# tron_disc.net
KiCad netlist of a schematic drawn in EAGLE
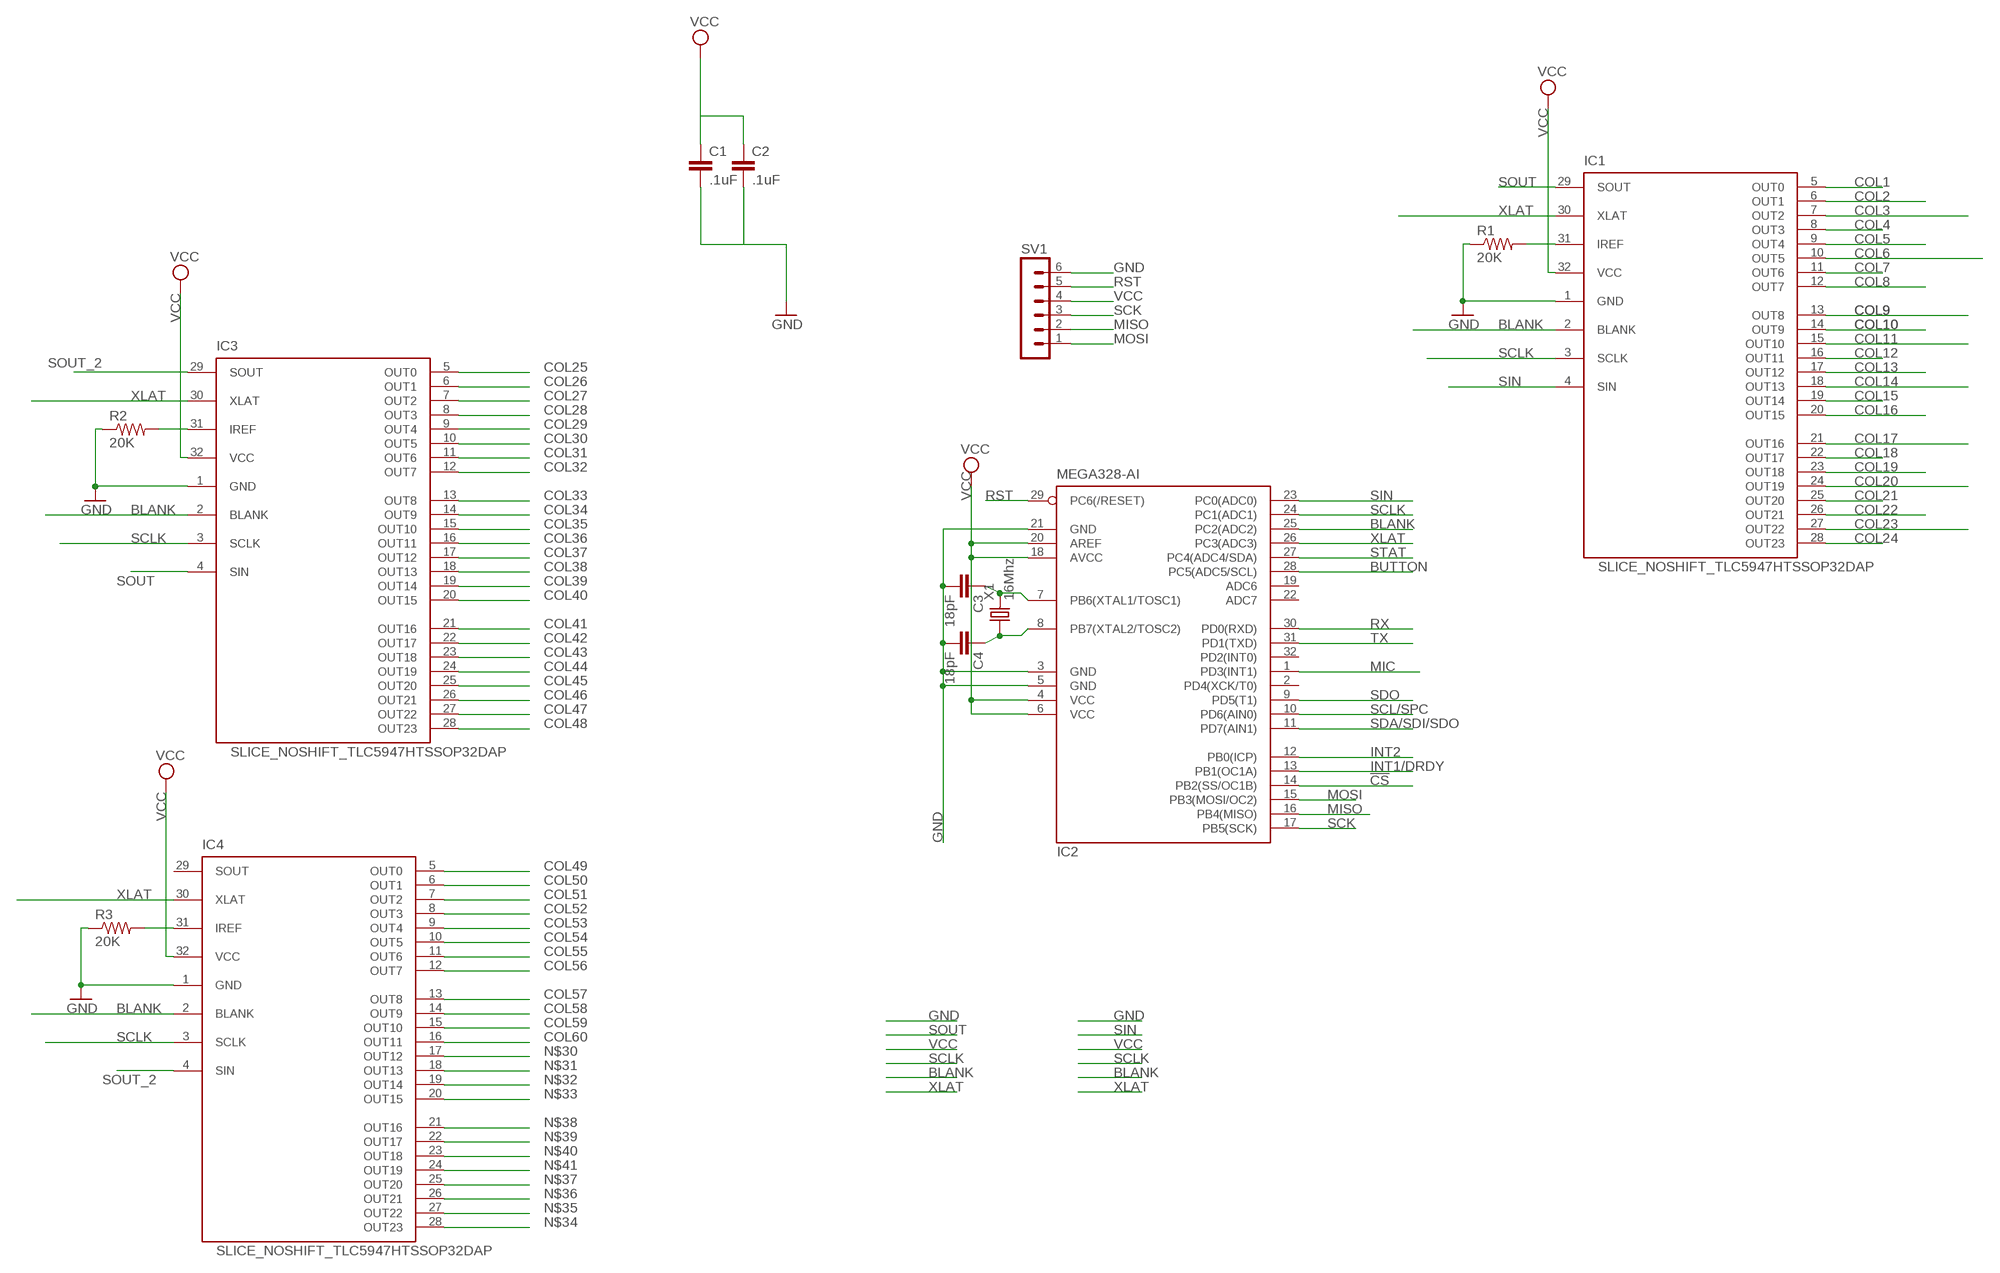
[diagram p0: schematic, sheet 1]
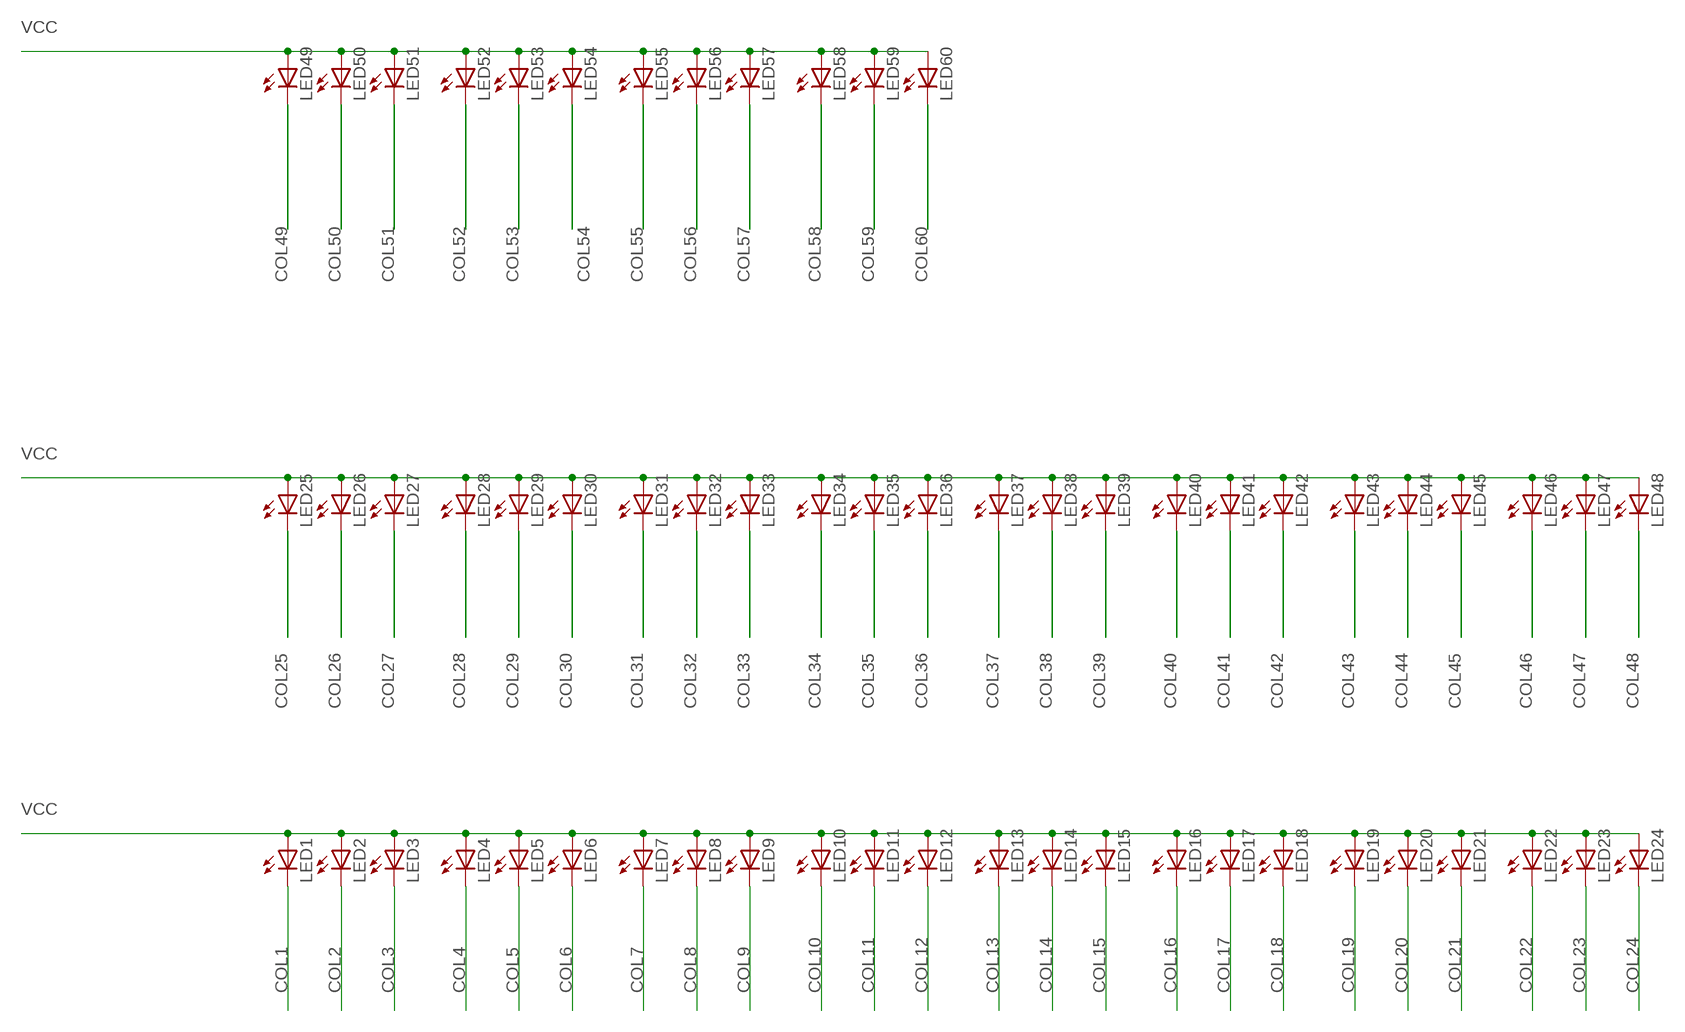
[diagram p1: schematic, sheet 2]
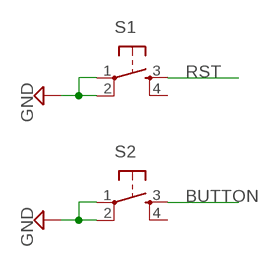
[diagram p2: schematic, sheet 3]

(export (version "E")
  (design (tool "Eeschema 10.0.6"))
  (components
    (comp (ref "S1")
      (value "TAC_SWITCHSMD")
      (footprint "eagle-import:TACTILE_SWITCH_SMD")
      (libsource (lib "eagle-import") (part "TAC_SWITCHSMD"))
    )
    (comp (ref "S2")
      (value "TAC_SWITCHSMD")
      (footprint "eagle-import:TACTILE_SWITCH_SMD")
      (libsource (lib "eagle-import") (part "TAC_SWITCHSMD"))
    )
    (comp (ref "C1")
      (value ".1uF")
      (footprint "eagle-import:0805")
      (libsource (lib "eagle-import") (part "CAP0805"))
    )
    (comp (ref "C2")
      (value ".1uF")
      (footprint "eagle-import:0805")
      (libsource (lib "eagle-import") (part "CAP0805"))
    )
    (comp (ref "C3")
      (value "18pF")
      (footprint "eagle-import:0805")
      (libsource (lib "eagle-import") (part "CAP0805"))
    )
    (comp (ref "C4")
      (value "18pF")
      (footprint "eagle-import:0805")
      (libsource (lib "eagle-import") (part "CAP0805"))
    )
    (comp (ref "IC1")
      (value "SLICE_NOSHIFT_TLC5947HTSSOP32DAP")
      (footprint "eagle-import:HTSSOP32DAP")
      (libsource (lib "eagle-import") (part "SLICE_NOSHIFT_TLC5947HTSSOP32DAP"))
    )
    (comp (ref "IC2")
      (value "MEGA328-AI")
      (footprint "eagle-import:TQFP32-08")
      (fields (field (name "MPN") "ATMEGA8-16AU"))
      (libsource (lib "eagle-import") (part "MEGA8-AI"))
    )
    (comp (ref "IC3")
      (value "SLICE_NOSHIFT_TLC5947HTSSOP32DAP")
      (footprint "eagle-import:HTSSOP32DAP")
      (libsource (lib "eagle-import") (part "SLICE_NOSHIFT_TLC5947HTSSOP32DAP"))
    )
    (comp (ref "IC4")
      (value "SLICE_NOSHIFT_TLC5947HTSSOP32DAP")
      (footprint "eagle-import:HTSSOP32DAP")
      (libsource (lib "eagle-import") (part "SLICE_NOSHIFT_TLC5947HTSSOP32DAP"))
    )
    (comp (ref "R1")
      (value "20K")
      (footprint "eagle-import:R0805")
      (libsource (lib "eagle-import") (part "R-US_R0805"))
    )
    (comp (ref "R2")
      (value "20K")
      (footprint "eagle-import:R0805")
      (libsource (lib "eagle-import") (part "R-US_R0805"))
    )
    (comp (ref "R3")
      (value "20K")
      (footprint "eagle-import:R0805")
      (libsource (lib "eagle-import") (part "R-US_R0805"))
    )
    (comp (ref "SV1")
      (value "MA06-1")
      (footprint "eagle-import:MA06-1")
      (libsource (lib "eagle-import") (part "MA06-1"))
    )
    (comp (ref "X1")
      (value "16Mhz")
      (footprint "eagle-import:5032")
      (libsource (lib "eagle-import") (part "CRYSTAL-5032"))
    )
    (comp (ref "LED1")
      (value "LEDCHIPLED_1206")
      (footprint "eagle-import:CHIPLED_1206")
      (libsource (lib "eagle-import") (part "LEDCHIPLED_1206"))
    )
    (comp (ref "LED2")
      (value "LEDCHIPLED_1206")
      (footprint "eagle-import:CHIPLED_1206")
      (libsource (lib "eagle-import") (part "LEDCHIPLED_1206"))
    )
    (comp (ref "LED3")
      (value "LEDCHIPLED_1206")
      (footprint "eagle-import:CHIPLED_1206")
      (libsource (lib "eagle-import") (part "LEDCHIPLED_1206"))
    )
    (comp (ref "LED4")
      (value "LEDCHIPLED_1206")
      (footprint "eagle-import:CHIPLED_1206")
      (libsource (lib "eagle-import") (part "LEDCHIPLED_1206"))
    )
    (comp (ref "LED5")
      (value "LEDCHIPLED_1206")
      (footprint "eagle-import:CHIPLED_1206")
      (libsource (lib "eagle-import") (part "LEDCHIPLED_1206"))
    )
    (comp (ref "LED6")
      (value "LEDCHIPLED_1206")
      (footprint "eagle-import:CHIPLED_1206")
      (libsource (lib "eagle-import") (part "LEDCHIPLED_1206"))
    )
    (comp (ref "LED7")
      (value "LEDCHIPLED_1206")
      (footprint "eagle-import:CHIPLED_1206")
      (libsource (lib "eagle-import") (part "LEDCHIPLED_1206"))
    )
    (comp (ref "LED8")
      (value "LEDCHIPLED_1206")
      (footprint "eagle-import:CHIPLED_1206")
      (libsource (lib "eagle-import") (part "LEDCHIPLED_1206"))
    )
    (comp (ref "LED9")
      (value "LEDCHIPLED_1206")
      (footprint "eagle-import:CHIPLED_1206")
      (libsource (lib "eagle-import") (part "LEDCHIPLED_1206"))
    )
    (comp (ref "LED10")
      (value "LEDCHIPLED_1206")
      (footprint "eagle-import:CHIPLED_1206")
      (libsource (lib "eagle-import") (part "LEDCHIPLED_1206"))
    )
    (comp (ref "LED11")
      (value "LEDCHIPLED_1206")
      (footprint "eagle-import:CHIPLED_1206")
      (libsource (lib "eagle-import") (part "LEDCHIPLED_1206"))
    )
    (comp (ref "LED12")
      (value "LEDCHIPLED_1206")
      (footprint "eagle-import:CHIPLED_1206")
      (libsource (lib "eagle-import") (part "LEDCHIPLED_1206"))
    )
    (comp (ref "LED13")
      (value "LEDCHIPLED_1206")
      (footprint "eagle-import:CHIPLED_1206")
      (libsource (lib "eagle-import") (part "LEDCHIPLED_1206"))
    )
    (comp (ref "LED14")
      (value "LEDCHIPLED_1206")
      (footprint "eagle-import:CHIPLED_1206")
      (libsource (lib "eagle-import") (part "LEDCHIPLED_1206"))
    )
    (comp (ref "LED15")
      (value "LEDCHIPLED_1206")
      (footprint "eagle-import:CHIPLED_1206")
      (libsource (lib "eagle-import") (part "LEDCHIPLED_1206"))
    )
    (comp (ref "LED16")
      (value "LEDCHIPLED_1206")
      (footprint "eagle-import:CHIPLED_1206")
      (libsource (lib "eagle-import") (part "LEDCHIPLED_1206"))
    )
    (comp (ref "LED17")
      (value "LEDCHIPLED_1206")
      (footprint "eagle-import:CHIPLED_1206")
      (libsource (lib "eagle-import") (part "LEDCHIPLED_1206"))
    )
    (comp (ref "LED18")
      (value "LEDCHIPLED_1206")
      (footprint "eagle-import:CHIPLED_1206")
      (libsource (lib "eagle-import") (part "LEDCHIPLED_1206"))
    )
    (comp (ref "LED19")
      (value "LEDCHIPLED_1206")
      (footprint "eagle-import:CHIPLED_1206")
      (libsource (lib "eagle-import") (part "LEDCHIPLED_1206"))
    )
    (comp (ref "LED20")
      (value "LEDCHIPLED_1206")
      (footprint "eagle-import:CHIPLED_1206")
      (libsource (lib "eagle-import") (part "LEDCHIPLED_1206"))
    )
    (comp (ref "LED21")
      (value "LEDCHIPLED_1206")
      (footprint "eagle-import:CHIPLED_1206")
      (libsource (lib "eagle-import") (part "LEDCHIPLED_1206"))
    )
    (comp (ref "LED22")
      (value "LEDCHIPLED_1206")
      (footprint "eagle-import:CHIPLED_1206")
      (libsource (lib "eagle-import") (part "LEDCHIPLED_1206"))
    )
    (comp (ref "LED23")
      (value "LEDCHIPLED_1206")
      (footprint "eagle-import:CHIPLED_1206")
      (libsource (lib "eagle-import") (part "LEDCHIPLED_1206"))
    )
    (comp (ref "LED24")
      (value "LEDCHIPLED_1206")
      (footprint "eagle-import:CHIPLED_1206")
      (libsource (lib "eagle-import") (part "LEDCHIPLED_1206"))
    )
    (comp (ref "LED25")
      (value "LEDCHIPLED_1206")
      (footprint "eagle-import:CHIPLED_1206")
      (libsource (lib "eagle-import") (part "LEDCHIPLED_1206"))
    )
    (comp (ref "LED26")
      (value "LEDCHIPLED_1206")
      (footprint "eagle-import:CHIPLED_1206")
      (libsource (lib "eagle-import") (part "LEDCHIPLED_1206"))
    )
    (comp (ref "LED27")
      (value "LEDCHIPLED_1206")
      (footprint "eagle-import:CHIPLED_1206")
      (libsource (lib "eagle-import") (part "LEDCHIPLED_1206"))
    )
    (comp (ref "LED28")
      (value "LEDCHIPLED_1206")
      (footprint "eagle-import:CHIPLED_1206")
      (libsource (lib "eagle-import") (part "LEDCHIPLED_1206"))
    )
    (comp (ref "LED29")
      (value "LEDCHIPLED_1206")
      (footprint "eagle-import:CHIPLED_1206")
      (libsource (lib "eagle-import") (part "LEDCHIPLED_1206"))
    )
    (comp (ref "LED30")
      (value "LEDCHIPLED_1206")
      (footprint "eagle-import:CHIPLED_1206")
      (libsource (lib "eagle-import") (part "LEDCHIPLED_1206"))
    )
    (comp (ref "LED31")
      (value "LEDCHIPLED_1206")
      (footprint "eagle-import:CHIPLED_1206")
      (libsource (lib "eagle-import") (part "LEDCHIPLED_1206"))
    )
    (comp (ref "LED32")
      (value "LEDCHIPLED_1206")
      (footprint "eagle-import:CHIPLED_1206")
      (libsource (lib "eagle-import") (part "LEDCHIPLED_1206"))
    )
    (comp (ref "LED33")
      (value "LEDCHIPLED_1206")
      (footprint "eagle-import:CHIPLED_1206")
      (libsource (lib "eagle-import") (part "LEDCHIPLED_1206"))
    )
    (comp (ref "LED34")
      (value "LEDCHIPLED_1206")
      (footprint "eagle-import:CHIPLED_1206")
      (libsource (lib "eagle-import") (part "LEDCHIPLED_1206"))
    )
    (comp (ref "LED35")
      (value "LEDCHIPLED_1206")
      (footprint "eagle-import:CHIPLED_1206")
      (libsource (lib "eagle-import") (part "LEDCHIPLED_1206"))
    )
    (comp (ref "LED36")
      (value "LEDCHIPLED_1206")
      (footprint "eagle-import:CHIPLED_1206")
      (libsource (lib "eagle-import") (part "LEDCHIPLED_1206"))
    )
    (comp (ref "LED37")
      (value "LEDCHIPLED_1206")
      (footprint "eagle-import:CHIPLED_1206")
      (libsource (lib "eagle-import") (part "LEDCHIPLED_1206"))
    )
    (comp (ref "LED38")
      (value "LEDCHIPLED_1206")
      (footprint "eagle-import:CHIPLED_1206")
      (libsource (lib "eagle-import") (part "LEDCHIPLED_1206"))
    )
    (comp (ref "LED39")
      (value "LEDCHIPLED_1206")
      (footprint "eagle-import:CHIPLED_1206")
      (libsource (lib "eagle-import") (part "LEDCHIPLED_1206"))
    )
    (comp (ref "LED40")
      (value "LEDCHIPLED_1206")
      (footprint "eagle-import:CHIPLED_1206")
      (libsource (lib "eagle-import") (part "LEDCHIPLED_1206"))
    )
    (comp (ref "LED41")
      (value "LEDCHIPLED_1206")
      (footprint "eagle-import:CHIPLED_1206")
      (libsource (lib "eagle-import") (part "LEDCHIPLED_1206"))
    )
    (comp (ref "LED42")
      (value "LEDCHIPLED_1206")
      (footprint "eagle-import:CHIPLED_1206")
      (libsource (lib "eagle-import") (part "LEDCHIPLED_1206"))
    )
    (comp (ref "LED43")
      (value "LEDCHIPLED_1206")
      (footprint "eagle-import:CHIPLED_1206")
      (libsource (lib "eagle-import") (part "LEDCHIPLED_1206"))
    )
    (comp (ref "LED44")
      (value "LEDCHIPLED_1206")
      (footprint "eagle-import:CHIPLED_1206")
      (libsource (lib "eagle-import") (part "LEDCHIPLED_1206"))
    )
    (comp (ref "LED45")
      (value "LEDCHIPLED_1206")
      (footprint "eagle-import:CHIPLED_1206")
      (libsource (lib "eagle-import") (part "LEDCHIPLED_1206"))
    )
    (comp (ref "LED46")
      (value "LEDCHIPLED_1206")
      (footprint "eagle-import:CHIPLED_1206")
      (libsource (lib "eagle-import") (part "LEDCHIPLED_1206"))
    )
    (comp (ref "LED47")
      (value "LEDCHIPLED_1206")
      (footprint "eagle-import:CHIPLED_1206")
      (libsource (lib "eagle-import") (part "LEDCHIPLED_1206"))
    )
    (comp (ref "LED48")
      (value "LEDCHIPLED_1206")
      (footprint "eagle-import:CHIPLED_1206")
      (libsource (lib "eagle-import") (part "LEDCHIPLED_1206"))
    )
    (comp (ref "LED49")
      (value "LEDCHIPLED_1206")
      (footprint "eagle-import:CHIPLED_1206")
      (libsource (lib "eagle-import") (part "LEDCHIPLED_1206"))
    )
    (comp (ref "LED50")
      (value "LEDCHIPLED_1206")
      (footprint "eagle-import:CHIPLED_1206")
      (libsource (lib "eagle-import") (part "LEDCHIPLED_1206"))
    )
    (comp (ref "LED51")
      (value "LEDCHIPLED_1206")
      (footprint "eagle-import:CHIPLED_1206")
      (libsource (lib "eagle-import") (part "LEDCHIPLED_1206"))
    )
    (comp (ref "LED52")
      (value "LEDCHIPLED_1206")
      (footprint "eagle-import:CHIPLED_1206")
      (libsource (lib "eagle-import") (part "LEDCHIPLED_1206"))
    )
    (comp (ref "LED53")
      (value "LEDCHIPLED_1206")
      (footprint "eagle-import:CHIPLED_1206")
      (libsource (lib "eagle-import") (part "LEDCHIPLED_1206"))
    )
    (comp (ref "LED54")
      (value "LEDCHIPLED_1206")
      (footprint "eagle-import:CHIPLED_1206")
      (libsource (lib "eagle-import") (part "LEDCHIPLED_1206"))
    )
    (comp (ref "LED55")
      (value "LEDCHIPLED_1206")
      (footprint "eagle-import:CHIPLED_1206")
      (libsource (lib "eagle-import") (part "LEDCHIPLED_1206"))
    )
    (comp (ref "LED56")
      (value "LEDCHIPLED_1206")
      (footprint "eagle-import:CHIPLED_1206")
      (libsource (lib "eagle-import") (part "LEDCHIPLED_1206"))
    )
    (comp (ref "LED57")
      (value "LEDCHIPLED_1206")
      (footprint "eagle-import:CHIPLED_1206")
      (libsource (lib "eagle-import") (part "LEDCHIPLED_1206"))
    )
    (comp (ref "LED58")
      (value "LEDCHIPLED_1206")
      (footprint "eagle-import:CHIPLED_1206")
      (libsource (lib "eagle-import") (part "LEDCHIPLED_1206"))
    )
    (comp (ref "LED59")
      (value "LEDCHIPLED_1206")
      (footprint "eagle-import:CHIPLED_1206")
      (libsource (lib "eagle-import") (part "LEDCHIPLED_1206"))
    )
    (comp (ref "LED60")
      (value "LEDCHIPLED_1206")
      (footprint "eagle-import:CHIPLED_1206")
      (libsource (lib "eagle-import") (part "LEDCHIPLED_1206"))
    )
  )
  (nets
    (net (code "1") (name "BLANK") (class "Default")
      (node (ref "IC1") (pin "2") (pinfunction "BLANK_2") (pintype "bidirectional"))
      (node (ref "IC2") (pin "25") (pinfunction "PC2(ADC2)_25") (pintype "bidirectional"))
      (node (ref "IC3") (pin "2") (pinfunction "BLANK_2") (pintype "bidirectional"))
      (node (ref "IC4") (pin "2") (pinfunction "BLANK_2") (pintype "bidirectional"))
    )
    (net (code "2") (name "BUTTON") (class "Default")
      (node (ref "IC2") (pin "28") (pinfunction "PC5(ADC5/SCL)_28") (pintype "bidirectional"))
      (node (ref "S2") (pin "3") (pinfunction "3_3") (pintype "passive"))
    )
    (net (code "3") (name "COL1") (class "Default")
      (node (ref "IC1") (pin "5") (pinfunction "OUT0_5") (pintype "bidirectional"))
      (node (ref "LED1") (pin "C") (pinfunction "C_C") (pintype "passive"))
    )
    (net (code "4") (name "COL2") (class "Default")
      (node (ref "IC1") (pin "6") (pinfunction "OUT1_6") (pintype "bidirectional"))
      (node (ref "LED2") (pin "C") (pinfunction "C_C") (pintype "passive"))
    )
    (net (code "5") (name "COL3") (class "Default")
      (node (ref "IC1") (pin "7") (pinfunction "OUT2_7") (pintype "bidirectional"))
      (node (ref "LED3") (pin "C") (pinfunction "C_C") (pintype "passive"))
    )
    (net (code "6") (name "COL4") (class "Default")
      (node (ref "IC1") (pin "8") (pinfunction "OUT3_8") (pintype "bidirectional"))
      (node (ref "LED4") (pin "C") (pinfunction "C_C") (pintype "passive"))
    )
    (net (code "7") (name "COL5") (class "Default")
      (node (ref "IC1") (pin "9") (pinfunction "OUT4_9") (pintype "bidirectional"))
      (node (ref "LED5") (pin "C") (pinfunction "C_C") (pintype "passive"))
    )
    (net (code "8") (name "COL6") (class "Default")
      (node (ref "IC1") (pin "10") (pinfunction "OUT5_10") (pintype "bidirectional"))
      (node (ref "LED6") (pin "C") (pinfunction "C_C") (pintype "passive"))
    )
    (net (code "9") (name "COL7") (class "Default")
      (node (ref "IC1") (pin "11") (pinfunction "OUT6_11") (pintype "bidirectional"))
      (node (ref "LED7") (pin "C") (pinfunction "C_C") (pintype "passive"))
    )
    (net (code "10") (name "COL8") (class "Default")
      (node (ref "IC1") (pin "12") (pinfunction "OUT7_12") (pintype "bidirectional"))
      (node (ref "LED8") (pin "C") (pinfunction "C_C") (pintype "passive"))
    )
    (net (code "11") (name "COL9") (class "Default")
      (node (ref "IC1") (pin "13") (pinfunction "OUT8_13") (pintype "bidirectional"))
      (node (ref "LED9") (pin "C") (pinfunction "C_C") (pintype "passive"))
    )
    (net (code "12") (name "COL10") (class "Default")
      (node (ref "IC1") (pin "14") (pinfunction "OUT9_14") (pintype "bidirectional"))
      (node (ref "LED10") (pin "C") (pinfunction "C_C") (pintype "passive"))
    )
    (net (code "13") (name "COL11") (class "Default")
      (node (ref "IC1") (pin "15") (pinfunction "OUT10_15") (pintype "bidirectional"))
      (node (ref "LED11") (pin "C") (pinfunction "C_C") (pintype "passive"))
    )
    (net (code "14") (name "COL12") (class "Default")
      (node (ref "IC1") (pin "16") (pinfunction "OUT11_16") (pintype "bidirectional"))
      (node (ref "LED12") (pin "C") (pinfunction "C_C") (pintype "passive"))
    )
    (net (code "15") (name "COL13") (class "Default")
      (node (ref "IC1") (pin "17") (pinfunction "OUT12_17") (pintype "bidirectional"))
      (node (ref "LED13") (pin "C") (pinfunction "C_C") (pintype "passive"))
    )
    (net (code "16") (name "COL14") (class "Default")
      (node (ref "IC1") (pin "18") (pinfunction "OUT13_18") (pintype "bidirectional"))
      (node (ref "LED14") (pin "C") (pinfunction "C_C") (pintype "passive"))
    )
    (net (code "17") (name "COL15") (class "Default")
      (node (ref "IC1") (pin "19") (pinfunction "OUT14_19") (pintype "bidirectional"))
      (node (ref "LED15") (pin "C") (pinfunction "C_C") (pintype "passive"))
    )
    (net (code "18") (name "COL16") (class "Default")
      (node (ref "IC1") (pin "20") (pinfunction "OUT15_20") (pintype "bidirectional"))
      (node (ref "LED16") (pin "C") (pinfunction "C_C") (pintype "passive"))
    )
    (net (code "19") (name "COL17") (class "Default")
      (node (ref "IC1") (pin "21") (pinfunction "OUT16_21") (pintype "bidirectional"))
      (node (ref "LED17") (pin "C") (pinfunction "C_C") (pintype "passive"))
    )
    (net (code "20") (name "COL18") (class "Default")
      (node (ref "IC1") (pin "22") (pinfunction "OUT17_22") (pintype "bidirectional"))
      (node (ref "LED18") (pin "C") (pinfunction "C_C") (pintype "passive"))
    )
    (net (code "21") (name "COL19") (class "Default")
      (node (ref "IC1") (pin "23") (pinfunction "OUT18_23") (pintype "bidirectional"))
      (node (ref "LED19") (pin "C") (pinfunction "C_C") (pintype "passive"))
    )
    (net (code "22") (name "COL20") (class "Default")
      (node (ref "IC1") (pin "24") (pinfunction "OUT19_24") (pintype "bidirectional"))
      (node (ref "LED20") (pin "C") (pinfunction "C_C") (pintype "passive"))
    )
    (net (code "23") (name "COL21") (class "Default")
      (node (ref "IC1") (pin "25") (pinfunction "OUT20_25") (pintype "bidirectional"))
      (node (ref "LED21") (pin "C") (pinfunction "C_C") (pintype "passive"))
    )
    (net (code "24") (name "COL22") (class "Default")
      (node (ref "IC1") (pin "26") (pinfunction "OUT21_26") (pintype "bidirectional"))
      (node (ref "LED22") (pin "C") (pinfunction "C_C") (pintype "passive"))
    )
    (net (code "25") (name "COL23") (class "Default")
      (node (ref "IC1") (pin "27") (pinfunction "OUT22_27") (pintype "bidirectional"))
      (node (ref "LED23") (pin "C") (pinfunction "C_C") (pintype "passive"))
    )
    (net (code "26") (name "COL24") (class "Default")
      (node (ref "IC1") (pin "28") (pinfunction "OUT23_28") (pintype "bidirectional"))
      (node (ref "LED24") (pin "C") (pinfunction "C_C") (pintype "passive"))
    )
    (net (code "27") (name "COL25") (class "Default")
      (node (ref "IC3") (pin "5") (pinfunction "OUT0_5") (pintype "bidirectional"))
      (node (ref "LED25") (pin "C") (pinfunction "C_C") (pintype "passive"))
    )
    (net (code "28") (name "COL26") (class "Default")
      (node (ref "IC3") (pin "6") (pinfunction "OUT1_6") (pintype "bidirectional"))
      (node (ref "LED26") (pin "C") (pinfunction "C_C") (pintype "passive"))
    )
    (net (code "29") (name "COL27") (class "Default")
      (node (ref "IC3") (pin "7") (pinfunction "OUT2_7") (pintype "bidirectional"))
      (node (ref "LED27") (pin "C") (pinfunction "C_C") (pintype "passive"))
    )
    (net (code "30") (name "COL28") (class "Default")
      (node (ref "IC3") (pin "8") (pinfunction "OUT3_8") (pintype "bidirectional"))
      (node (ref "LED28") (pin "C") (pinfunction "C_C") (pintype "passive"))
    )
    (net (code "31") (name "COL29") (class "Default")
      (node (ref "IC3") (pin "9") (pinfunction "OUT4_9") (pintype "bidirectional"))
      (node (ref "LED29") (pin "C") (pinfunction "C_C") (pintype "passive"))
    )
    (net (code "32") (name "COL30") (class "Default")
      (node (ref "IC3") (pin "10") (pinfunction "OUT5_10") (pintype "bidirectional"))
      (node (ref "LED30") (pin "C") (pinfunction "C_C") (pintype "passive"))
    )
    (net (code "33") (name "COL31") (class "Default")
      (node (ref "IC3") (pin "11") (pinfunction "OUT6_11") (pintype "bidirectional"))
      (node (ref "LED31") (pin "C") (pinfunction "C_C") (pintype "passive"))
    )
    (net (code "34") (name "COL32") (class "Default")
      (node (ref "IC3") (pin "12") (pinfunction "OUT7_12") (pintype "bidirectional"))
      (node (ref "LED32") (pin "C") (pinfunction "C_C") (pintype "passive"))
    )
    (net (code "35") (name "COL33") (class "Default")
      (node (ref "IC3") (pin "13") (pinfunction "OUT8_13") (pintype "bidirectional"))
      (node (ref "LED33") (pin "C") (pinfunction "C_C") (pintype "passive"))
    )
    (net (code "36") (name "COL34") (class "Default")
      (node (ref "IC3") (pin "14") (pinfunction "OUT9_14") (pintype "bidirectional"))
      (node (ref "LED34") (pin "C") (pinfunction "C_C") (pintype "passive"))
    )
    (net (code "37") (name "COL35") (class "Default")
      (node (ref "IC3") (pin "15") (pinfunction "OUT10_15") (pintype "bidirectional"))
      (node (ref "LED35") (pin "C") (pinfunction "C_C") (pintype "passive"))
    )
    (net (code "38") (name "COL36") (class "Default")
      (node (ref "IC3") (pin "16") (pinfunction "OUT11_16") (pintype "bidirectional"))
      (node (ref "LED36") (pin "C") (pinfunction "C_C") (pintype "passive"))
    )
    (net (code "39") (name "COL37") (class "Default")
      (node (ref "IC3") (pin "17") (pinfunction "OUT12_17") (pintype "bidirectional"))
      (node (ref "LED37") (pin "C") (pinfunction "C_C") (pintype "passive"))
    )
    (net (code "40") (name "COL38") (class "Default")
      (node (ref "IC3") (pin "18") (pinfunction "OUT13_18") (pintype "bidirectional"))
      (node (ref "LED38") (pin "C") (pinfunction "C_C") (pintype "passive"))
    )
    (net (code "41") (name "COL39") (class "Default")
      (node (ref "IC3") (pin "19") (pinfunction "OUT14_19") (pintype "bidirectional"))
      (node (ref "LED39") (pin "C") (pinfunction "C_C") (pintype "passive"))
    )
    (net (code "42") (name "COL40") (class "Default")
      (node (ref "IC3") (pin "20") (pinfunction "OUT15_20") (pintype "bidirectional"))
      (node (ref "LED40") (pin "C") (pinfunction "C_C") (pintype "passive"))
    )
    (net (code "43") (name "COL41") (class "Default")
      (node (ref "IC3") (pin "21") (pinfunction "OUT16_21") (pintype "bidirectional"))
      (node (ref "LED41") (pin "C") (pinfunction "C_C") (pintype "passive"))
    )
    (net (code "44") (name "COL42") (class "Default")
      (node (ref "IC3") (pin "22") (pinfunction "OUT17_22") (pintype "bidirectional"))
      (node (ref "LED42") (pin "C") (pinfunction "C_C") (pintype "passive"))
    )
    (net (code "45") (name "COL43") (class "Default")
      (node (ref "IC3") (pin "23") (pinfunction "OUT18_23") (pintype "bidirectional"))
      (node (ref "LED43") (pin "C") (pinfunction "C_C") (pintype "passive"))
    )
    (net (code "46") (name "COL44") (class "Default")
      (node (ref "IC3") (pin "24") (pinfunction "OUT19_24") (pintype "bidirectional"))
      (node (ref "LED44") (pin "C") (pinfunction "C_C") (pintype "passive"))
    )
    (net (code "47") (name "COL45") (class "Default")
      (node (ref "IC3") (pin "25") (pinfunction "OUT20_25") (pintype "bidirectional"))
      (node (ref "LED45") (pin "C") (pinfunction "C_C") (pintype "passive"))
    )
    (net (code "48") (name "COL46") (class "Default")
      (node (ref "IC3") (pin "26") (pinfunction "OUT21_26") (pintype "bidirectional"))
      (node (ref "LED46") (pin "C") (pinfunction "C_C") (pintype "passive"))
    )
    (net (code "49") (name "COL47") (class "Default")
      (node (ref "IC3") (pin "27") (pinfunction "OUT22_27") (pintype "bidirectional"))
      (node (ref "LED47") (pin "C") (pinfunction "C_C") (pintype "passive"))
    )
    (net (code "50") (name "COL48") (class "Default")
      (node (ref "IC3") (pin "28") (pinfunction "OUT23_28") (pintype "bidirectional"))
      (node (ref "LED48") (pin "C") (pinfunction "C_C") (pintype "passive"))
    )
    (net (code "51") (name "COL49") (class "Default")
      (node (ref "IC4") (pin "5") (pinfunction "OUT0_5") (pintype "bidirectional"))
      (node (ref "LED49") (pin "C") (pinfunction "C_C") (pintype "passive"))
    )
    (net (code "52") (name "COL50") (class "Default")
      (node (ref "IC4") (pin "6") (pinfunction "OUT1_6") (pintype "bidirectional"))
      (node (ref "LED50") (pin "C") (pinfunction "C_C") (pintype "passive"))
    )
    (net (code "53") (name "COL51") (class "Default")
      (node (ref "IC4") (pin "7") (pinfunction "OUT2_7") (pintype "bidirectional"))
      (node (ref "LED51") (pin "C") (pinfunction "C_C") (pintype "passive"))
    )
    (net (code "54") (name "COL52") (class "Default")
      (node (ref "IC4") (pin "8") (pinfunction "OUT3_8") (pintype "bidirectional"))
      (node (ref "LED52") (pin "C") (pinfunction "C_C") (pintype "passive"))
    )
    (net (code "55") (name "COL53") (class "Default")
      (node (ref "IC4") (pin "9") (pinfunction "OUT4_9") (pintype "bidirectional"))
      (node (ref "LED53") (pin "C") (pinfunction "C_C") (pintype "passive"))
    )
    (net (code "56") (name "COL54") (class "Default")
      (node (ref "IC4") (pin "10") (pinfunction "OUT5_10") (pintype "bidirectional"))
      (node (ref "LED54") (pin "C") (pinfunction "C_C") (pintype "passive"))
    )
    (net (code "57") (name "COL55") (class "Default")
      (node (ref "IC4") (pin "11") (pinfunction "OUT6_11") (pintype "bidirectional"))
      (node (ref "LED55") (pin "C") (pinfunction "C_C") (pintype "passive"))
    )
    (net (code "58") (name "COL56") (class "Default")
      (node (ref "IC4") (pin "12") (pinfunction "OUT7_12") (pintype "bidirectional"))
      (node (ref "LED56") (pin "C") (pinfunction "C_C") (pintype "passive"))
    )
    (net (code "59") (name "COL57") (class "Default")
      (node (ref "IC4") (pin "13") (pinfunction "OUT8_13") (pintype "bidirectional"))
      (node (ref "LED57") (pin "C") (pinfunction "C_C") (pintype "passive"))
    )
    (net (code "60") (name "COL58") (class "Default")
      (node (ref "IC4") (pin "14") (pinfunction "OUT9_14") (pintype "bidirectional"))
      (node (ref "LED58") (pin "C") (pinfunction "C_C") (pintype "passive"))
    )
    (net (code "61") (name "COL59") (class "Default")
      (node (ref "IC4") (pin "15") (pinfunction "OUT10_15") (pintype "bidirectional"))
      (node (ref "LED59") (pin "C") (pinfunction "C_C") (pintype "passive"))
    )
    (net (code "62") (name "COL60") (class "Default")
      (node (ref "IC4") (pin "16") (pinfunction "OUT11_16") (pintype "bidirectional"))
      (node (ref "LED60") (pin "C") (pinfunction "C_C") (pintype "passive"))
    )
    (net (code "63") (name "GND") (class "Default")
      (node (ref "C1") (pin "2") (pinfunction "2_2") (pintype "passive"))
      (node (ref "C2") (pin "2") (pinfunction "2_2") (pintype "passive"))
      (node (ref "C3") (pin "2") (pinfunction "2_2") (pintype "passive"))
      (node (ref "C4") (pin "2") (pinfunction "2_2") (pintype "passive"))
      (node (ref "IC1") (pin "1") (pinfunction "GND_1") (pintype "bidirectional"))
      (node (ref "IC2") (pin "21") (pinfunction "GND_21") (pintype "power_in"))
      (node (ref "IC2") (pin "3") (pinfunction "GND_3") (pintype "power_in"))
      (node (ref "IC2") (pin "5") (pinfunction "GND_5") (pintype "power_in"))
      (node (ref "IC3") (pin "1") (pinfunction "GND_1") (pintype "bidirectional"))
      (node (ref "IC4") (pin "1") (pinfunction "GND_1") (pintype "bidirectional"))
      (node (ref "R1") (pin "1") (pinfunction "1_1") (pintype "passive"))
      (node (ref "R2") (pin "1") (pinfunction "1_1") (pintype "passive"))
      (node (ref "R3") (pin "1") (pinfunction "1_1") (pintype "passive"))
      (node (ref "S1") (pin "1") (pinfunction "1_1") (pintype "passive"))
      (node (ref "S1") (pin "2") (pinfunction "2_2") (pintype "passive"))
      (node (ref "S2") (pin "1") (pinfunction "1_1") (pintype "passive"))
      (node (ref "S2") (pin "2") (pinfunction "2_2") (pintype "passive"))
      (node (ref "SV1") (pin "6") (pinfunction "6_6") (pintype "passive"))
    )
    (net (code "64") (name "INT1{slash}DRDY") (class "Default")
      (node (ref "IC2") (pin "13") (pinfunction "PB1(OC1A)_13") (pintype "bidirectional"))
    )
    (net (code "65") (name "INT2") (class "Default")
      (node (ref "IC2") (pin "12") (pinfunction "PB0(ICP)_12") (pintype "bidirectional"))
    )
    (net (code "66") (name "MIC") (class "Default")
      (node (ref "IC2") (pin "1") (pinfunction "PD3(INT1)_1") (pintype "bidirectional"))
    )
    (net (code "67") (name "MISO") (class "Default")
      (node (ref "IC2") (pin "16") (pinfunction "PB4(MISO)_16") (pintype "bidirectional"))
      (node (ref "SV1") (pin "2") (pinfunction "2_2") (pintype "passive"))
    )
    (net (code "68") (name "MOSI") (class "Default")
      (node (ref "IC2") (pin "15") (pinfunction "PB3(MOSI/OC2)_15") (pintype "bidirectional"))
      (node (ref "SV1") (pin "1") (pinfunction "1_1") (pintype "passive"))
    )
    (net (code "69") (name "N$30") (class "Default")
      (node (ref "IC4") (pin "17") (pinfunction "OUT12_17") (pintype "bidirectional"))
    )
    (net (code "70") (name "N$31") (class "Default")
      (node (ref "IC4") (pin "18") (pinfunction "OUT13_18") (pintype "bidirectional"))
    )
    (net (code "71") (name "N$32") (class "Default")
      (node (ref "IC4") (pin "19") (pinfunction "OUT14_19") (pintype "bidirectional"))
    )
    (net (code "72") (name "N$33") (class "Default")
      (node (ref "IC4") (pin "20") (pinfunction "OUT15_20") (pintype "bidirectional"))
    )
    (net (code "73") (name "N$34") (class "Default")
      (node (ref "IC4") (pin "28") (pinfunction "OUT23_28") (pintype "bidirectional"))
    )
    (net (code "74") (name "N$35") (class "Default")
      (node (ref "IC4") (pin "27") (pinfunction "OUT22_27") (pintype "bidirectional"))
    )
    (net (code "75") (name "N$36") (class "Default")
      (node (ref "IC4") (pin "26") (pinfunction "OUT21_26") (pintype "bidirectional"))
    )
    (net (code "76") (name "N$37") (class "Default")
      (node (ref "IC4") (pin "25") (pinfunction "OUT20_25") (pintype "bidirectional"))
    )
    (net (code "77") (name "N$38") (class "Default")
      (node (ref "IC4") (pin "21") (pinfunction "OUT16_21") (pintype "bidirectional"))
    )
    (net (code "78") (name "N$39") (class "Default")
      (node (ref "IC4") (pin "22") (pinfunction "OUT17_22") (pintype "bidirectional"))
    )
    (net (code "79") (name "N$40") (class "Default")
      (node (ref "IC4") (pin "23") (pinfunction "OUT18_23") (pintype "bidirectional"))
    )
    (net (code "80") (name "N$41") (class "Default")
      (node (ref "IC4") (pin "24") (pinfunction "OUT19_24") (pintype "bidirectional"))
    )
    (net (code "81") (name "Net-(IC1-IREF)") (class "Default")
      (node (ref "IC1") (pin "31") (pinfunction "IREF_31") (pintype "bidirectional"))
      (node (ref "R1") (pin "2") (pinfunction "2_2") (pintype "passive"))
    )
    (net (code "82") (name "Net-(IC2-PB6(XTAL1{slash}TOSC1))") (class "Default")
      (node (ref "C3") (pin "1") (pinfunction "1_1") (pintype "passive"))
      (node (ref "IC2") (pin "7") (pinfunction "PB6(XTAL1/TOSC1)_7") (pintype "bidirectional"))
      (node (ref "X1") (pin "2") (pinfunction "2_2") (pintype "passive"))
    )
    (net (code "83") (name "Net-(IC2-PB7(XTAL2{slash}TOSC2))") (class "Default")
      (node (ref "C4") (pin "1") (pinfunction "1_1") (pintype "passive"))
      (node (ref "IC2") (pin "8") (pinfunction "PB7(XTAL2/TOSC2)_8") (pintype "bidirectional"))
      (node (ref "X1") (pin "1") (pinfunction "1_1") (pintype "passive"))
    )
    (net (code "84") (name "Net-(IC3-IREF)") (class "Default")
      (node (ref "IC3") (pin "31") (pinfunction "IREF_31") (pintype "bidirectional"))
      (node (ref "R2") (pin "2") (pinfunction "2_2") (pintype "passive"))
    )
    (net (code "85") (name "Net-(IC4-IREF)") (class "Default")
      (node (ref "IC4") (pin "31") (pinfunction "IREF_31") (pintype "bidirectional"))
      (node (ref "R3") (pin "2") (pinfunction "2_2") (pintype "passive"))
    )
    (net (code "86") (name "RST") (class "Default")
      (node (ref "IC2") (pin "29") (pinfunction "PC6(/RESET)_29") (pintype "bidirectional"))
      (node (ref "S1") (pin "3") (pinfunction "3_3") (pintype "passive"))
      (node (ref "SV1") (pin "5") (pinfunction "5_5") (pintype "passive"))
    )
    (net (code "87") (name "RX") (class "Default")
      (node (ref "IC2") (pin "30") (pinfunction "PD0(RXD)_30") (pintype "bidirectional"))
    )
    (net (code "88") (name "SCK") (class "Default")
      (node (ref "IC2") (pin "17") (pinfunction "PB5(SCK)_17") (pintype "bidirectional"))
      (node (ref "SV1") (pin "3") (pinfunction "3_3") (pintype "passive"))
    )
    (net (code "89") (name "SCLK") (class "Default")
      (node (ref "IC1") (pin "3") (pinfunction "SCLK_3") (pintype "bidirectional"))
      (node (ref "IC2") (pin "24") (pinfunction "PC1(ADC1)_24") (pintype "bidirectional"))
      (node (ref "IC3") (pin "3") (pinfunction "SCLK_3") (pintype "bidirectional"))
      (node (ref "IC4") (pin "3") (pinfunction "SCLK_3") (pintype "bidirectional"))
    )
    (net (code "90") (name "SCL{slash}SPC") (class "Default")
      (node (ref "IC2") (pin "10") (pinfunction "PD6(AIN0)_10") (pintype "bidirectional"))
    )
    (net (code "91") (name "SDA{slash}SDI{slash}SDO") (class "Default")
      (node (ref "IC2") (pin "11") (pinfunction "PD7(AIN1)_11") (pintype "bidirectional"))
    )
    (net (code "92") (name "SDO") (class "Default")
      (node (ref "IC2") (pin "9") (pinfunction "PD5(T1)_9") (pintype "bidirectional"))
    )
    (net (code "93") (name "SIN") (class "Default")
      (node (ref "IC1") (pin "4") (pinfunction "SIN_4") (pintype "bidirectional"))
      (node (ref "IC2") (pin "23") (pinfunction "PC0(ADC0)_23") (pintype "bidirectional"))
    )
    (net (code "94") (name "SOUT") (class "Default")
      (node (ref "IC1") (pin "29") (pinfunction "SOUT_29") (pintype "bidirectional"))
      (node (ref "IC3") (pin "4") (pinfunction "SIN_4") (pintype "bidirectional"))
    )
    (net (code "95") (name "SOUT_2") (class "Default")
      (node (ref "IC3") (pin "29") (pinfunction "SOUT_29") (pintype "bidirectional"))
      (node (ref "IC4") (pin "4") (pinfunction "SIN_4") (pintype "bidirectional"))
    )
    (net (code "96") (name "STAT") (class "Default")
      (node (ref "IC2") (pin "27") (pinfunction "PC4(ADC4/SDA)_27") (pintype "bidirectional"))
    )
    (net (code "97") (name "TX") (class "Default")
      (node (ref "IC2") (pin "31") (pinfunction "PD1(TXD)_31") (pintype "bidirectional"))
    )
    (net (code "98") (name "VCC") (class "Default")
      (node (ref "C1") (pin "1") (pinfunction "1_1") (pintype "passive"))
      (node (ref "C2") (pin "1") (pinfunction "1_1") (pintype "passive"))
      (node (ref "IC1") (pin "32") (pinfunction "VCC_32") (pintype "bidirectional"))
      (node (ref "IC2") (pin "18") (pinfunction "AVCC_18") (pintype "power_in"))
      (node (ref "IC2") (pin "20") (pinfunction "AREF_20") (pintype "passive"))
      (node (ref "IC2") (pin "4") (pinfunction "VCC_4") (pintype "power_in"))
      (node (ref "IC2") (pin "6") (pinfunction "VCC_6") (pintype "power_in"))
      (node (ref "IC3") (pin "32") (pinfunction "VCC_32") (pintype "bidirectional"))
      (node (ref "IC4") (pin "32") (pinfunction "VCC_32") (pintype "bidirectional"))
      (node (ref "LED1") (pin "A") (pinfunction "A_A") (pintype "passive"))
      (node (ref "LED10") (pin "A") (pinfunction "A_A") (pintype "passive"))
      (node (ref "LED11") (pin "A") (pinfunction "A_A") (pintype "passive"))
      (node (ref "LED12") (pin "A") (pinfunction "A_A") (pintype "passive"))
      (node (ref "LED13") (pin "A") (pinfunction "A_A") (pintype "passive"))
      (node (ref "LED14") (pin "A") (pinfunction "A_A") (pintype "passive"))
      (node (ref "LED15") (pin "A") (pinfunction "A_A") (pintype "passive"))
      (node (ref "LED16") (pin "A") (pinfunction "A_A") (pintype "passive"))
      (node (ref "LED17") (pin "A") (pinfunction "A_A") (pintype "passive"))
      (node (ref "LED18") (pin "A") (pinfunction "A_A") (pintype "passive"))
      (node (ref "LED19") (pin "A") (pinfunction "A_A") (pintype "passive"))
      (node (ref "LED2") (pin "A") (pinfunction "A_A") (pintype "passive"))
      (node (ref "LED20") (pin "A") (pinfunction "A_A") (pintype "passive"))
      (node (ref "LED21") (pin "A") (pinfunction "A_A") (pintype "passive"))
      (node (ref "LED22") (pin "A") (pinfunction "A_A") (pintype "passive"))
      (node (ref "LED23") (pin "A") (pinfunction "A_A") (pintype "passive"))
      (node (ref "LED24") (pin "A") (pinfunction "A_A") (pintype "passive"))
      (node (ref "LED25") (pin "A") (pinfunction "A_A") (pintype "passive"))
      (node (ref "LED26") (pin "A") (pinfunction "A_A") (pintype "passive"))
      (node (ref "LED27") (pin "A") (pinfunction "A_A") (pintype "passive"))
      (node (ref "LED28") (pin "A") (pinfunction "A_A") (pintype "passive"))
      (node (ref "LED29") (pin "A") (pinfunction "A_A") (pintype "passive"))
      (node (ref "LED3") (pin "A") (pinfunction "A_A") (pintype "passive"))
      (node (ref "LED30") (pin "A") (pinfunction "A_A") (pintype "passive"))
      (node (ref "LED31") (pin "A") (pinfunction "A_A") (pintype "passive"))
      (node (ref "LED32") (pin "A") (pinfunction "A_A") (pintype "passive"))
      (node (ref "LED33") (pin "A") (pinfunction "A_A") (pintype "passive"))
      (node (ref "LED34") (pin "A") (pinfunction "A_A") (pintype "passive"))
      (node (ref "LED35") (pin "A") (pinfunction "A_A") (pintype "passive"))
      (node (ref "LED36") (pin "A") (pinfunction "A_A") (pintype "passive"))
      (node (ref "LED37") (pin "A") (pinfunction "A_A") (pintype "passive"))
      (node (ref "LED38") (pin "A") (pinfunction "A_A") (pintype "passive"))
      (node (ref "LED39") (pin "A") (pinfunction "A_A") (pintype "passive"))
      (node (ref "LED4") (pin "A") (pinfunction "A_A") (pintype "passive"))
      (node (ref "LED40") (pin "A") (pinfunction "A_A") (pintype "passive"))
      (node (ref "LED41") (pin "A") (pinfunction "A_A") (pintype "passive"))
      (node (ref "LED42") (pin "A") (pinfunction "A_A") (pintype "passive"))
      (node (ref "LED43") (pin "A") (pinfunction "A_A") (pintype "passive"))
      (node (ref "LED44") (pin "A") (pinfunction "A_A") (pintype "passive"))
      (node (ref "LED45") (pin "A") (pinfunction "A_A") (pintype "passive"))
      (node (ref "LED46") (pin "A") (pinfunction "A_A") (pintype "passive"))
      (node (ref "LED47") (pin "A") (pinfunction "A_A") (pintype "passive"))
      (node (ref "LED48") (pin "A") (pinfunction "A_A") (pintype "passive"))
      (node (ref "LED49") (pin "A") (pinfunction "A_A") (pintype "passive"))
      (node (ref "LED5") (pin "A") (pinfunction "A_A") (pintype "passive"))
      (node (ref "LED50") (pin "A") (pinfunction "A_A") (pintype "passive"))
      (node (ref "LED51") (pin "A") (pinfunction "A_A") (pintype "passive"))
      (node (ref "LED52") (pin "A") (pinfunction "A_A") (pintype "passive"))
      (node (ref "LED53") (pin "A") (pinfunction "A_A") (pintype "passive"))
      (node (ref "LED54") (pin "A") (pinfunction "A_A") (pintype "passive"))
      (node (ref "LED55") (pin "A") (pinfunction "A_A") (pintype "passive"))
      (node (ref "LED56") (pin "A") (pinfunction "A_A") (pintype "passive"))
      (node (ref "LED57") (pin "A") (pinfunction "A_A") (pintype "passive"))
      (node (ref "LED58") (pin "A") (pinfunction "A_A") (pintype "passive"))
      (node (ref "LED59") (pin "A") (pinfunction "A_A") (pintype "passive"))
      (node (ref "LED6") (pin "A") (pinfunction "A_A") (pintype "passive"))
      (node (ref "LED60") (pin "A") (pinfunction "A_A") (pintype "passive"))
      (node (ref "LED7") (pin "A") (pinfunction "A_A") (pintype "passive"))
      (node (ref "LED8") (pin "A") (pinfunction "A_A") (pintype "passive"))
      (node (ref "LED9") (pin "A") (pinfunction "A_A") (pintype "passive"))
      (node (ref "SV1") (pin "4") (pinfunction "4_4") (pintype "passive"))
    )
    (net (code "99") (name "XLAT") (class "Default")
      (node (ref "IC1") (pin "30") (pinfunction "XLAT_30") (pintype "bidirectional"))
      (node (ref "IC2") (pin "26") (pinfunction "PC3(ADC3)_26") (pintype "bidirectional"))
      (node (ref "IC3") (pin "30") (pinfunction "XLAT_30") (pintype "bidirectional"))
      (node (ref "IC4") (pin "30") (pinfunction "XLAT_30") (pintype "bidirectional"))
    )
    (net (code "100") (name "unconnected-(IC2-ADC6-Pad19)") (class "Default")
      (node (ref "IC2") (pin "19") (pinfunction "ADC6_19") (pintype "bidirectional"))
    )
    (net (code "101") (name "unconnected-(IC2-ADC7-Pad22)") (class "Default")
      (node (ref "IC2") (pin "22") (pinfunction "ADC7_22") (pintype "bidirectional"))
    )
    (net (code "102") (name "unconnected-(IC2-PD2(INT0)-Pad32)") (class "Default")
      (node (ref "IC2") (pin "32") (pinfunction "PD2(INT0)_32") (pintype "bidirectional"))
    )
    (net (code "103") (name "unconnected-(IC2-PD4(XCK{slash}T0)-Pad2)") (class "Default")
      (node (ref "IC2") (pin "2") (pinfunction "PD4(XCK/T0)_2") (pintype "bidirectional"))
    )
    (net (code "104") (name "unconnected-(IC4-SOUT-Pad29)") (class "Default")
      (node (ref "IC4") (pin "29") (pinfunction "SOUT_29") (pintype "bidirectional"))
    )
    (net (code "105") (name "unconnected-(S1-Pad4)") (class "Default")
      (node (ref "S1") (pin "4") (pinfunction "4_4") (pintype "passive"))
    )
    (net (code "106") (name "unconnected-(S2-Pad4)") (class "Default")
      (node (ref "S2") (pin "4") (pinfunction "4_4") (pintype "passive"))
    )
    (net (code "107") (name "~{CS}") (class "Default")
      (node (ref "IC2") (pin "14") (pinfunction "PB2(SS/OC1B)_14") (pintype "bidirectional"))
    )
  )
)
